# Encoder_respaldos.net
KiCad netlist of a schematic drawn in EAGLE
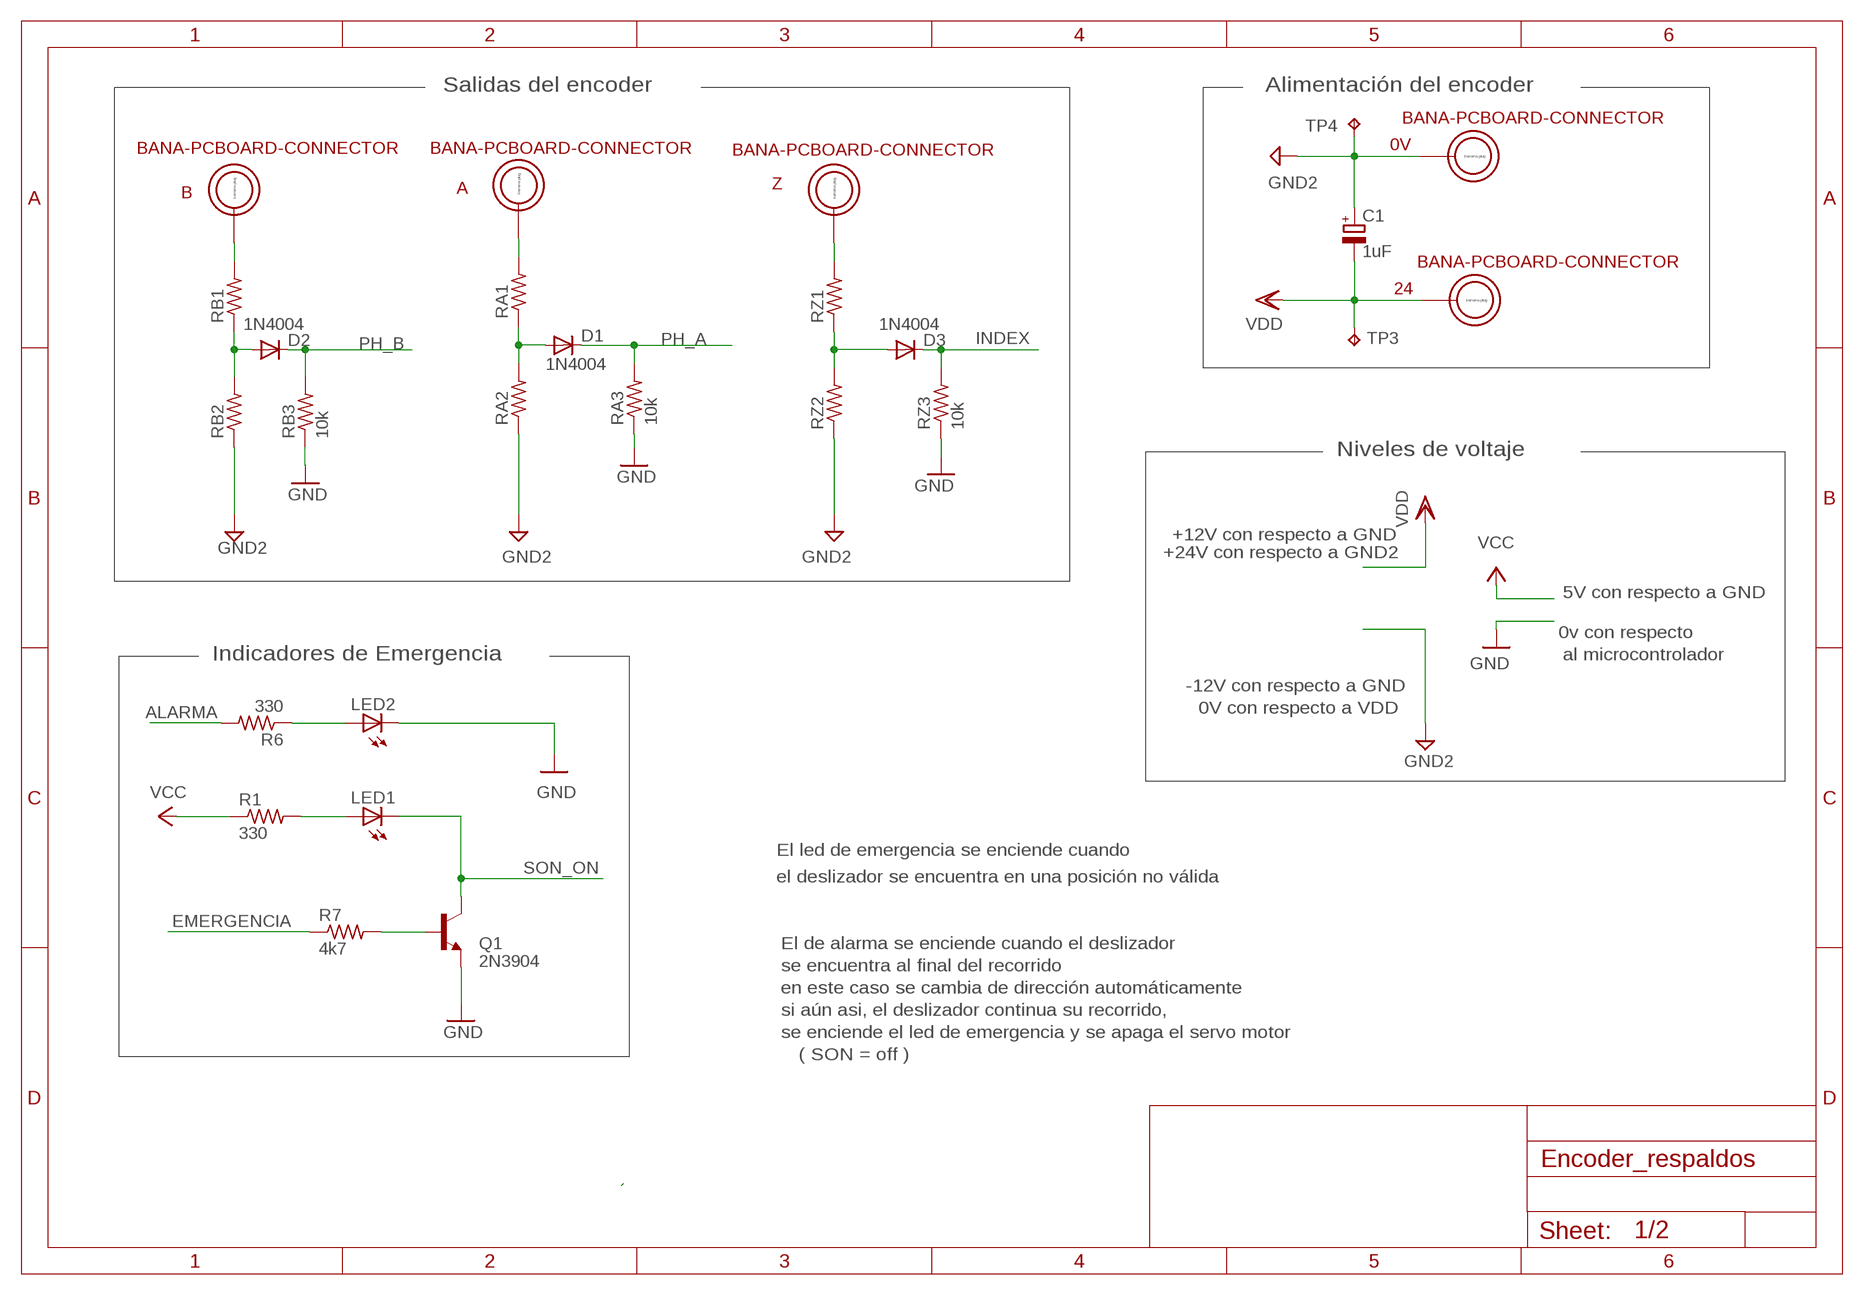
[diagram p0: schematic, sheet 1]
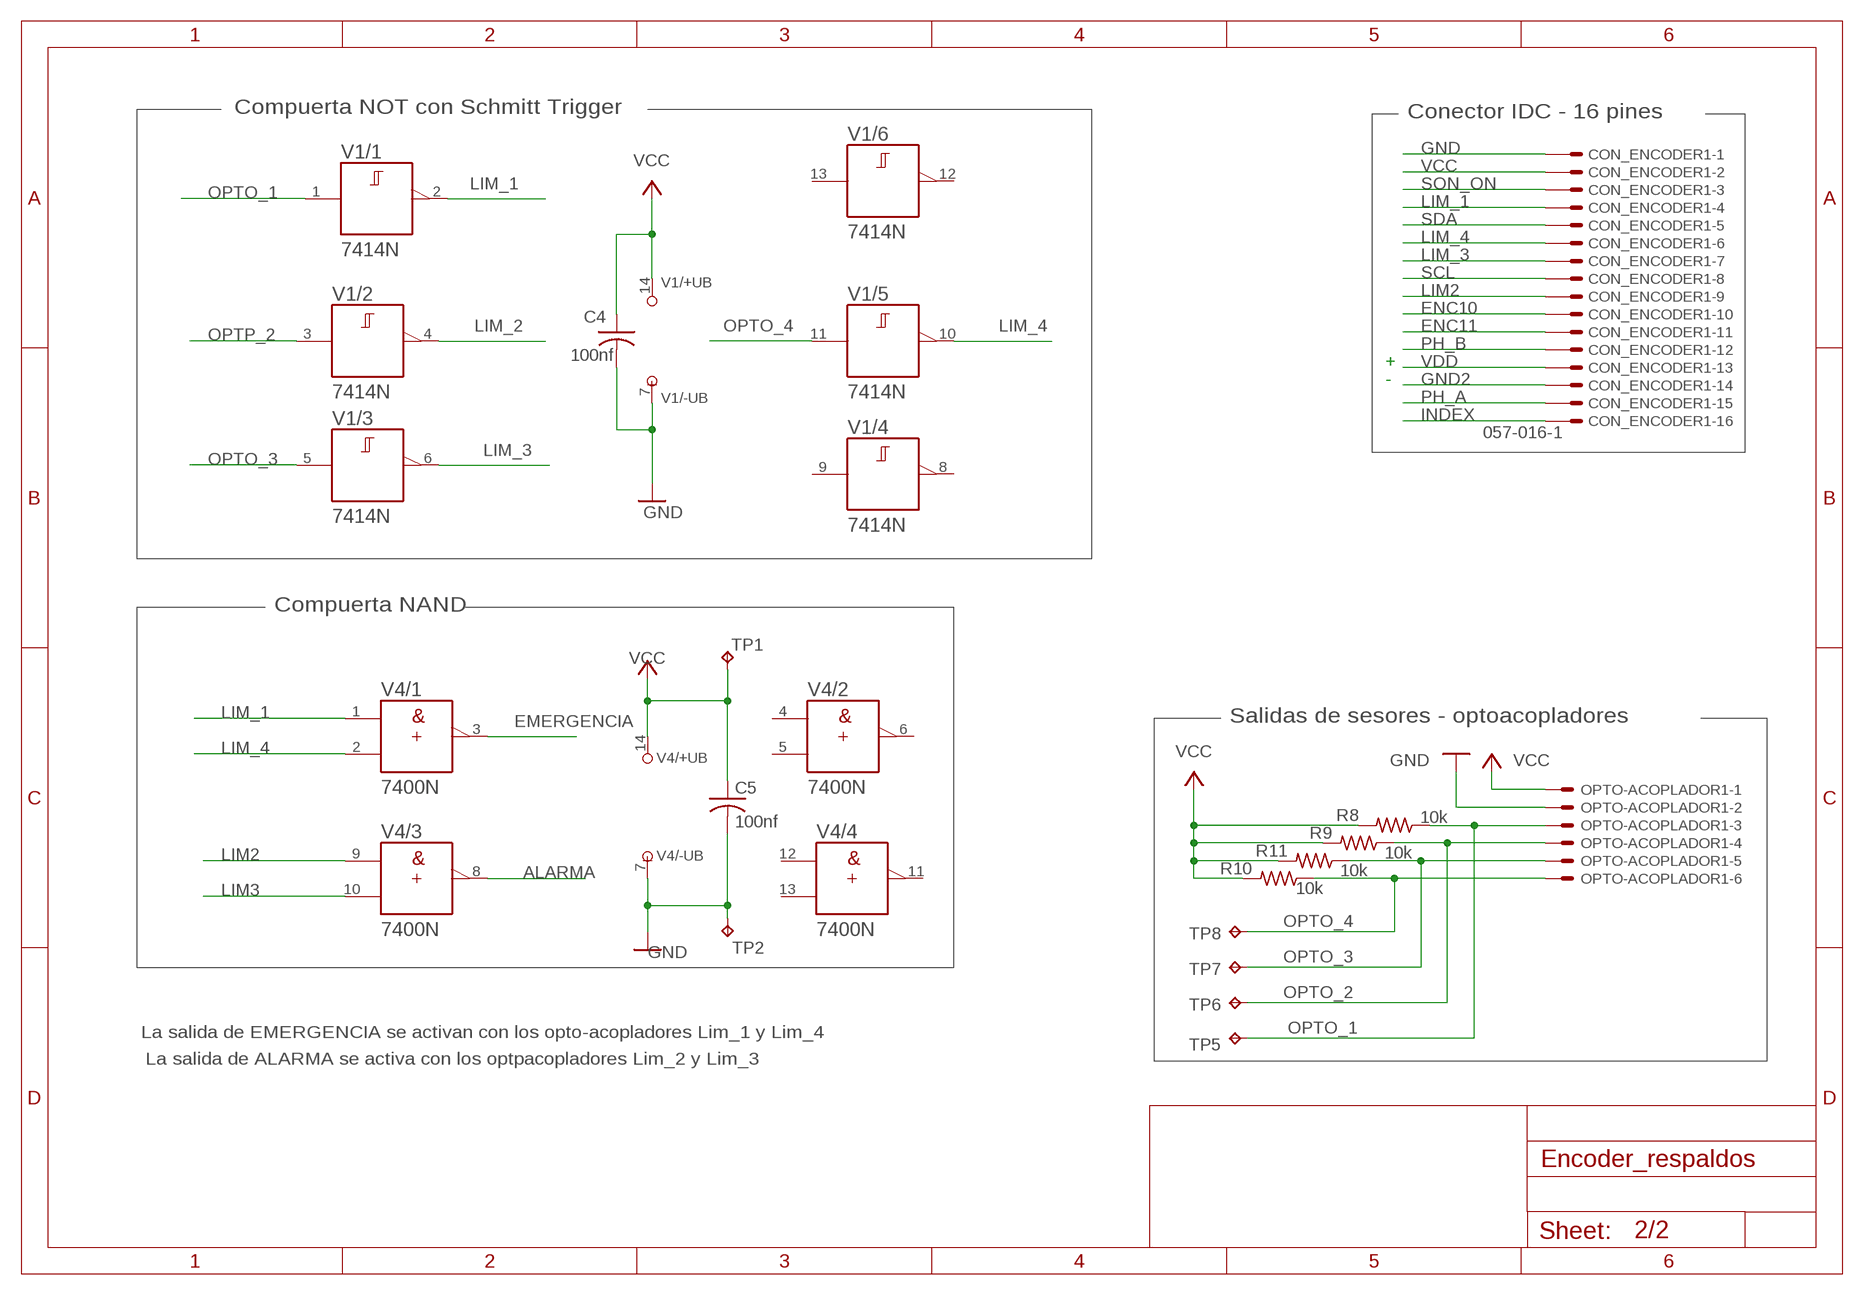
[diagram p1: schematic, sheet 2]

(export (version "E")
  (design (tool "Eeschema 10.0.6"))
  (components
    (comp (ref "0V")
      (value "BANA-PCBOARD-CONNECTOR")
      (footprint "eagle-import:BANA_PLUG")
      (libsource (lib "eagle-import") (part "BANA-PCBOARD-CONNECTOR"))
    )
    (comp (ref "24")
      (value "BANA-PCBOARD-CONNECTOR")
      (footprint "eagle-import:BANA_PLUG")
      (libsource (lib "eagle-import") (part "BANA-PCBOARD-CONNECTOR"))
    )
    (comp (ref "A")
      (value "BANA-PCBOARD-CONNECTOR")
      (footprint "eagle-import:BANA_PLUG")
      (libsource (lib "eagle-import") (part "BANA-PCBOARD-CONNECTOR"))
    )
    (comp (ref "B")
      (value "BANA-PCBOARD-CONNECTOR")
      (footprint "eagle-import:BANA_PLUG")
      (libsource (lib "eagle-import") (part "BANA-PCBOARD-CONNECTOR"))
    )
    (comp (ref "C1")
      (value "1uF")
      (footprint "eagle-import:E2,5-6")
      (libsource (lib "eagle-import") (part "CPOL-EUE2.5-6"))
    )
    (comp (ref "D1")
      (value "1N4004")
      (footprint "eagle-import:DO41-10")
      (libsource (lib "eagle-import") (part "1N4004"))
    )
    (comp (ref "D2")
      (value "1N4004")
      (footprint "eagle-import:DO41-10")
      (libsource (lib "eagle-import") (part "1N4004"))
    )
    (comp (ref "D3")
      (value "1N4004")
      (footprint "eagle-import:DO41-10")
      (libsource (lib "eagle-import") (part "1N4004"))
    )
    (comp (ref "LED1")
      (value "LED5MM")
      (footprint "eagle-import:LED5MM")
      (libsource (lib "eagle-import") (part "LED5MM"))
    )
    (comp (ref "LED2")
      (value "LED5MM")
      (footprint "eagle-import:LED5MM")
      (libsource (lib "eagle-import") (part "LED5MM"))
    )
    (comp (ref "Q1")
      (value "2N3904")
      (footprint "eagle-import:TO92")
      (libsource (lib "eagle-import") (part "2N3904"))
    )
    (comp (ref "R1")
      (value "330")
      (footprint "eagle-import:0204_7")
      (libsource (lib "eagle-import") (part "R-US_0204/7"))
    )
    (comp (ref "R6")
      (value "330")
      (footprint "eagle-import:0204_7")
      (libsource (lib "eagle-import") (part "R-US_0204/7"))
    )
    (comp (ref "R7")
      (value "4k7")
      (footprint "eagle-import:0204_7")
      (libsource (lib "eagle-import") (part "R-US_0204/7"))
    )
    (comp (ref "RA1")
      (value "R-US_0204/7")
      (footprint "eagle-import:0204_7")
      (libsource (lib "eagle-import") (part "R-US_0204/7"))
    )
    (comp (ref "RA2")
      (value "R-US_0204/7")
      (footprint "eagle-import:0204_7")
      (libsource (lib "eagle-import") (part "R-US_0204/7"))
    )
    (comp (ref "RA3")
      (value "10k")
      (footprint "eagle-import:0204_7")
      (libsource (lib "eagle-import") (part "R-US_0204/7"))
    )
    (comp (ref "RB1")
      (value "R-US_0204/7")
      (footprint "eagle-import:0204_7")
      (libsource (lib "eagle-import") (part "R-US_0204/7"))
    )
    (comp (ref "RB2")
      (value "R-US_0204/7")
      (footprint "eagle-import:0204_7")
      (libsource (lib "eagle-import") (part "R-US_0204/7"))
    )
    (comp (ref "RB3")
      (value "10k")
      (footprint "eagle-import:0204_7")
      (libsource (lib "eagle-import") (part "R-US_0204/7"))
    )
    (comp (ref "RZ1")
      (value "R-US_0204/7")
      (footprint "eagle-import:0204_7")
      (libsource (lib "eagle-import") (part "R-US_0204/7"))
    )
    (comp (ref "RZ2")
      (value "R-US_0204/7")
      (footprint "eagle-import:0204_7")
      (libsource (lib "eagle-import") (part "R-US_0204/7"))
    )
    (comp (ref "RZ3")
      (value "10k")
      (footprint "eagle-import:0204_7")
      (libsource (lib "eagle-import") (part "R-US_0204/7"))
    )
    (comp (ref "TP3")
      (value "TPB2,54")
      (footprint "eagle-import:B2,54")
      (libsource (lib "eagle-import") (part "TPB2,54"))
    )
    (comp (ref "TP4")
      (value "TPB2,54")
      (footprint "eagle-import:B2,54")
      (libsource (lib "eagle-import") (part "TPB2,54"))
    )
    (comp (ref "Z")
      (value "BANA-PCBOARD-CONNECTOR")
      (footprint "eagle-import:BANA_PLUG")
      (libsource (lib "eagle-import") (part "BANA-PCBOARD-CONNECTOR"))
    )
    (comp (ref "C4")
      (value "100nf")
      (footprint "eagle-import:C025-024X044")
      (libsource (lib "eagle-import") (part "C-US025-024X044"))
    )
    (comp (ref "C5")
      (value "100nf")
      (footprint "eagle-import:C025-024X044")
      (libsource (lib "eagle-import") (part "C-US025-024X044"))
    )
    (comp (ref "CON_ENCODER1")
      (value "057-016-1")
      (footprint "eagle-import:057-016-1")
      (libsource (lib "eagle-import") (part "057-016-1"))
    )
    (comp (ref "OPTO-ACOPLADOR1")
      (value "22-23-2061")
      (footprint "eagle-import:22-23-2061")
      (fields (field (name "MF") "MOLEX"))
      (libsource (lib "eagle-import") (part "22-23-2061"))
    )
    (comp (ref "R8")
      (value "10k")
      (footprint "eagle-import:0204_7")
      (libsource (lib "eagle-import") (part "R-US_0204/7"))
    )
    (comp (ref "R9")
      (value "10k")
      (footprint "eagle-import:0204_7")
      (libsource (lib "eagle-import") (part "R-US_0204/7"))
    )
    (comp (ref "R10")
      (value "10k")
      (footprint "eagle-import:0204_7")
      (libsource (lib "eagle-import") (part "R-US_0204/7"))
    )
    (comp (ref "R11")
      (value "10k")
      (footprint "eagle-import:0204_7")
      (libsource (lib "eagle-import") (part "R-US_0204/7"))
    )
    (comp (ref "TP1")
      (value "TPB2,54")
      (footprint "eagle-import:B2,54")
      (libsource (lib "eagle-import") (part "TPB2,54"))
    )
    (comp (ref "TP2")
      (value "TPB2,54")
      (footprint "eagle-import:B2,54")
      (libsource (lib "eagle-import") (part "TPB2,54"))
    )
    (comp (ref "TP5")
      (value "TPB2,54")
      (footprint "eagle-import:B2,54")
      (libsource (lib "eagle-import") (part "TPB2,54"))
    )
    (comp (ref "TP6")
      (value "TPB2,54")
      (footprint "eagle-import:B2,54")
      (libsource (lib "eagle-import") (part "TPB2,54"))
    )
    (comp (ref "TP7")
      (value "TPB2,54")
      (footprint "eagle-import:B2,54")
      (libsource (lib "eagle-import") (part "TPB2,54"))
    )
    (comp (ref "TP8")
      (value "TPB2,54")
      (footprint "eagle-import:B2,54")
      (libsource (lib "eagle-import") (part "TPB2,54"))
    )
    (comp (ref "V1")
      (value "7414N")
      (footprint "eagle-import:DIL14")
      (libsource (lib "eagle-import") (part "7414N"))
    )
    (comp (ref "V4")
      (value "7400N")
      (footprint "eagle-import:DIL14")
      (libsource (lib "eagle-import") (part "7400N"))
    )
  )
  (nets
    (net (code "1") (name "ALARMA") (class "Default")
      (node (ref "R6") (pin "2") (pinfunction "2_2") (pintype "passive"))
      (node (ref "V4") (pin "8") (pinfunction "Y_8") (pintype "output"))
    )
    (net (code "2") (name "EMERGENCIA") (class "Default")
      (node (ref "R7") (pin "1") (pinfunction "1_1") (pintype "passive"))
      (node (ref "V4") (pin "3") (pinfunction "Y_3") (pintype "output"))
    )
    (net (code "3") (name "ENC10") (class "Default")
      (node (ref "CON_ENCODER1") (pin "10") (pinfunction "S_10") (pintype "passive"))
    )
    (net (code "4") (name "ENC11") (class "Default")
      (node (ref "CON_ENCODER1") (pin "11") (pinfunction "S_11") (pintype "passive"))
    )
    (net (code "5") (name "GND") (class "Default")
      (node (ref "C4") (pin "2") (pinfunction "2_2") (pintype "passive"))
      (node (ref "C5") (pin "2") (pinfunction "2_2") (pintype "passive"))
      (node (ref "CON_ENCODER1") (pin "1") (pinfunction "S_1") (pintype "passive"))
      (node (ref "LED2") (pin "K") (pinfunction "C_K") (pintype "passive"))
      (node (ref "OPTO-ACOPLADOR1") (pin "2") (pinfunction "S_2") (pintype "passive"))
      (node (ref "Q1") (pin "3") (pinfunction "E_3") (pintype "passive"))
      (node (ref "RA3") (pin "1") (pinfunction "1_1") (pintype "passive"))
      (node (ref "RB3") (pin "1") (pinfunction "1_1") (pintype "passive"))
      (node (ref "RZ3") (pin "1") (pinfunction "1_1") (pintype "passive"))
      (node (ref "TP2") (pin "TP") (pinfunction "TP_TP") (pintype "input"))
      (node (ref "V1") (pin "7") (pinfunction "-UB_7") (pintype "power_in"))
      (node (ref "V4") (pin "7") (pinfunction "-UB_7") (pintype "power_in"))
    )
    (net (code "6") (name "GND2") (class "Default")
      (node (ref "0V") (pin "P$1") (pinfunction "P$1_P$1") (pintype "bidirectional"))
      (node (ref "C1") (pin "+") (pinfunction "+_+") (pintype "passive"))
      (node (ref "CON_ENCODER1") (pin "14") (pinfunction "S_14") (pintype "passive"))
      (node (ref "RA2") (pin "1") (pinfunction "1_1") (pintype "passive"))
      (node (ref "RB2") (pin "1") (pinfunction "1_1") (pintype "passive"))
      (node (ref "RZ2") (pin "1") (pinfunction "1_1") (pintype "passive"))
      (node (ref "TP4") (pin "TP") (pinfunction "TP_TP") (pintype "input"))
    )
    (net (code "7") (name "INDEX") (class "Default")
      (node (ref "CON_ENCODER1") (pin "16") (pinfunction "S_16") (pintype "passive"))
      (node (ref "D3") (pin "C") (pinfunction "C_C") (pintype "passive"))
      (node (ref "RZ3") (pin "2") (pinfunction "2_2") (pintype "passive"))
    )
    (net (code "8") (name "LIM2") (class "Default")
      (node (ref "CON_ENCODER1") (pin "9") (pinfunction "S_9") (pintype "passive"))
      (node (ref "V4") (pin "9") (pinfunction "A_9") (pintype "input"))
    )
    (net (code "9") (name "LIM3") (class "Default")
      (node (ref "V4") (pin "10") (pinfunction "B_10") (pintype "input"))
    )
    (net (code "10") (name "LIM_1") (class "Default")
      (node (ref "CON_ENCODER1") (pin "4") (pinfunction "S_4") (pintype "passive"))
      (node (ref "V1") (pin "2") (pinfunction "Y_2") (pintype "output"))
      (node (ref "V4") (pin "1") (pinfunction "A_1") (pintype "input"))
    )
    (net (code "11") (name "LIM_2") (class "Default")
      (node (ref "V1") (pin "4") (pinfunction "Y_4") (pintype "output"))
    )
    (net (code "12") (name "LIM_3") (class "Default")
      (node (ref "CON_ENCODER1") (pin "7") (pinfunction "S_7") (pintype "passive"))
      (node (ref "V1") (pin "6") (pinfunction "Y_6") (pintype "output"))
    )
    (net (code "13") (name "LIM_4") (class "Default")
      (node (ref "CON_ENCODER1") (pin "6") (pinfunction "S_6") (pintype "passive"))
      (node (ref "V1") (pin "10") (pinfunction "Y_10") (pintype "output"))
      (node (ref "V4") (pin "2") (pinfunction "B_2") (pintype "input"))
    )
    (net (code "14") (name "Net-(A-PadP$1)") (class "Default")
      (node (ref "A") (pin "P$1") (pinfunction "P$1_P$1") (pintype "bidirectional"))
      (node (ref "RA1") (pin "2") (pinfunction "2_2") (pintype "passive"))
    )
    (net (code "15") (name "Net-(B-PadP$1)") (class "Default")
      (node (ref "B") (pin "P$1") (pinfunction "P$1_P$1") (pintype "bidirectional"))
      (node (ref "RB1") (pin "2") (pinfunction "2_2") (pintype "passive"))
    )
    (net (code "16") (name "Net-(D1-PadA)") (class "Default")
      (node (ref "D1") (pin "A") (pinfunction "A_A") (pintype "passive"))
      (node (ref "RA1") (pin "1") (pinfunction "1_1") (pintype "passive"))
      (node (ref "RA2") (pin "2") (pinfunction "2_2") (pintype "passive"))
    )
    (net (code "17") (name "Net-(D2-PadA)") (class "Default")
      (node (ref "D2") (pin "A") (pinfunction "A_A") (pintype "passive"))
      (node (ref "RB1") (pin "1") (pinfunction "1_1") (pintype "passive"))
      (node (ref "RB2") (pin "2") (pinfunction "2_2") (pintype "passive"))
    )
    (net (code "18") (name "Net-(D3-PadA)") (class "Default")
      (node (ref "D3") (pin "A") (pinfunction "A_A") (pintype "passive"))
      (node (ref "RZ1") (pin "1") (pinfunction "1_1") (pintype "passive"))
      (node (ref "RZ2") (pin "2") (pinfunction "2_2") (pintype "passive"))
    )
    (net (code "19") (name "Net-(LED1-PadA)") (class "Default")
      (node (ref "LED1") (pin "A") (pinfunction "A_A") (pintype "passive"))
      (node (ref "R1") (pin "2") (pinfunction "2_2") (pintype "passive"))
    )
    (net (code "20") (name "Net-(LED2-PadA)") (class "Default")
      (node (ref "LED2") (pin "A") (pinfunction "A_A") (pintype "passive"))
      (node (ref "R6") (pin "1") (pinfunction "1_1") (pintype "passive"))
    )
    (net (code "21") (name "Net-(Q1-B)") (class "Default")
      (node (ref "Q1") (pin "2") (pinfunction "B_2") (pintype "passive"))
      (node (ref "R7") (pin "2") (pinfunction "2_2") (pintype "passive"))
    )
    (net (code "22") (name "Net-(RZ1-Pad2)") (class "Default")
      (node (ref "RZ1") (pin "2") (pinfunction "2_2") (pintype "passive"))
      (node (ref "Z") (pin "P$1") (pinfunction "P$1_P$1") (pintype "bidirectional"))
    )
    (net (code "23") (name "OPTO_1") (class "Default")
      (node (ref "OPTO-ACOPLADOR1") (pin "3") (pinfunction "S_3") (pintype "passive"))
      (node (ref "R8") (pin "1") (pinfunction "1_1") (pintype "passive"))
      (node (ref "TP5") (pin "TP") (pinfunction "TP_TP") (pintype "input"))
      (node (ref "V1") (pin "1") (pinfunction "A_1") (pintype "input"))
    )
    (net (code "24") (name "OPTO_2") (class "Default")
      (node (ref "OPTO-ACOPLADOR1") (pin "4") (pinfunction "S_4") (pintype "passive"))
      (node (ref "R9") (pin "1") (pinfunction "1_1") (pintype "passive"))
      (node (ref "TP6") (pin "TP") (pinfunction "TP_TP") (pintype "input"))
    )
    (net (code "25") (name "OPTO_3") (class "Default")
      (node (ref "OPTO-ACOPLADOR1") (pin "5") (pinfunction "S_5") (pintype "passive"))
      (node (ref "R11") (pin "1") (pinfunction "1_1") (pintype "passive"))
      (node (ref "TP7") (pin "TP") (pinfunction "TP_TP") (pintype "input"))
      (node (ref "V1") (pin "5") (pinfunction "A_5") (pintype "input"))
    )
    (net (code "26") (name "OPTO_4") (class "Default")
      (node (ref "OPTO-ACOPLADOR1") (pin "6") (pinfunction "S_6") (pintype "passive"))
      (node (ref "R10") (pin "1") (pinfunction "1_1") (pintype "passive"))
      (node (ref "TP8") (pin "TP") (pinfunction "TP_TP") (pintype "input"))
      (node (ref "V1") (pin "11") (pinfunction "A_11") (pintype "input"))
    )
    (net (code "27") (name "OPTP_2") (class "Default")
      (node (ref "V1") (pin "3") (pinfunction "A_3") (pintype "input"))
    )
    (net (code "28") (name "PH_A") (class "Default")
      (node (ref "CON_ENCODER1") (pin "15") (pinfunction "S_15") (pintype "passive"))
      (node (ref "D1") (pin "C") (pinfunction "C_C") (pintype "passive"))
      (node (ref "RA3") (pin "2") (pinfunction "2_2") (pintype "passive"))
    )
    (net (code "29") (name "PH_B") (class "Default")
      (node (ref "CON_ENCODER1") (pin "12") (pinfunction "S_12") (pintype "passive"))
      (node (ref "D2") (pin "C") (pinfunction "C_C") (pintype "passive"))
      (node (ref "RB3") (pin "2") (pinfunction "2_2") (pintype "passive"))
    )
    (net (code "30") (name "SCL") (class "Default")
      (node (ref "CON_ENCODER1") (pin "8") (pinfunction "S_8") (pintype "passive"))
    )
    (net (code "31") (name "SDA") (class "Default")
      (node (ref "CON_ENCODER1") (pin "5") (pinfunction "S_5") (pintype "passive"))
    )
    (net (code "32") (name "SON_ON") (class "Default")
      (node (ref "CON_ENCODER1") (pin "3") (pinfunction "S_3") (pintype "passive"))
      (node (ref "LED1") (pin "K") (pinfunction "C_K") (pintype "passive"))
      (node (ref "Q1") (pin "1") (pinfunction "C_1") (pintype "passive"))
    )
    (net (code "33") (name "VCC") (class "Default")
      (node (ref "C4") (pin "1") (pinfunction "1_1") (pintype "passive"))
      (node (ref "C5") (pin "1") (pinfunction "1_1") (pintype "passive"))
      (node (ref "CON_ENCODER1") (pin "2") (pinfunction "S_2") (pintype "passive"))
      (node (ref "OPTO-ACOPLADOR1") (pin "1") (pinfunction "S_1") (pintype "passive"))
      (node (ref "R1") (pin "1") (pinfunction "1_1") (pintype "passive"))
      (node (ref "R10") (pin "2") (pinfunction "2_2") (pintype "passive"))
      (node (ref "R11") (pin "2") (pinfunction "2_2") (pintype "passive"))
      (node (ref "R8") (pin "2") (pinfunction "2_2") (pintype "passive"))
      (node (ref "R9") (pin "2") (pinfunction "2_2") (pintype "passive"))
      (node (ref "TP1") (pin "TP") (pinfunction "TP_TP") (pintype "input"))
      (node (ref "V1") (pin "14") (pinfunction "+UB_14") (pintype "power_in"))
      (node (ref "V4") (pin "14") (pinfunction "+UB_14") (pintype "power_in"))
    )
    (net (code "34") (name "VDD") (class "Default")
      (node (ref "24") (pin "P$1") (pinfunction "P$1_P$1") (pintype "bidirectional"))
      (node (ref "C1") (pin "-") (pinfunction "-_-") (pintype "passive"))
      (node (ref "CON_ENCODER1") (pin "13") (pinfunction "S_13") (pintype "passive"))
      (node (ref "TP3") (pin "TP") (pinfunction "TP_TP") (pintype "input"))
    )
    (net (code "35") (name "unconnected-(V1F-A-Pad9)") (class "Default")
      (node (ref "V1") (pin "9") (pinfunction "A_9") (pintype "input"))
    )
    (net (code "36") (name "unconnected-(V1F-Y-Pad8)") (class "Default")
      (node (ref "V1") (pin "8") (pinfunction "Y_8") (pintype "output"))
    )
    (net (code "37") (name "unconnected-(V1H-A-Pad13)") (class "Default")
      (node (ref "V1") (pin "13") (pinfunction "A_13") (pintype "input"))
    )
    (net (code "38") (name "unconnected-(V1H-Y-Pad12)") (class "Default")
      (node (ref "V1") (pin "12") (pinfunction "Y_12") (pintype "output"))
    )
    (net (code "39") (name "unconnected-(V4D-A-Pad4)") (class "Default")
      (node (ref "V4") (pin "4") (pinfunction "A_4") (pintype "input"))
    )
    (net (code "40") (name "unconnected-(V4D-B-Pad5)") (class "Default")
      (node (ref "V4") (pin "5") (pinfunction "B_5") (pintype "input"))
    )
    (net (code "41") (name "unconnected-(V4D-Y-Pad6)") (class "Default")
      (node (ref "V4") (pin "6") (pinfunction "Y_6") (pintype "output"))
    )
    (net (code "42") (name "unconnected-(V4F-A-Pad12)") (class "Default")
      (node (ref "V4") (pin "12") (pinfunction "A_12") (pintype "input"))
    )
    (net (code "43") (name "unconnected-(V4F-B-Pad13)") (class "Default")
      (node (ref "V4") (pin "13") (pinfunction "B_13") (pintype "input"))
    )
    (net (code "44") (name "unconnected-(V4F-Y-Pad11)") (class "Default")
      (node (ref "V4") (pin "11") (pinfunction "Y_11") (pintype "output"))
    )
  )
)
